# Counter_Display_v2_OLD.net
KiCad netlist of a schematic drawn in Altium Designer
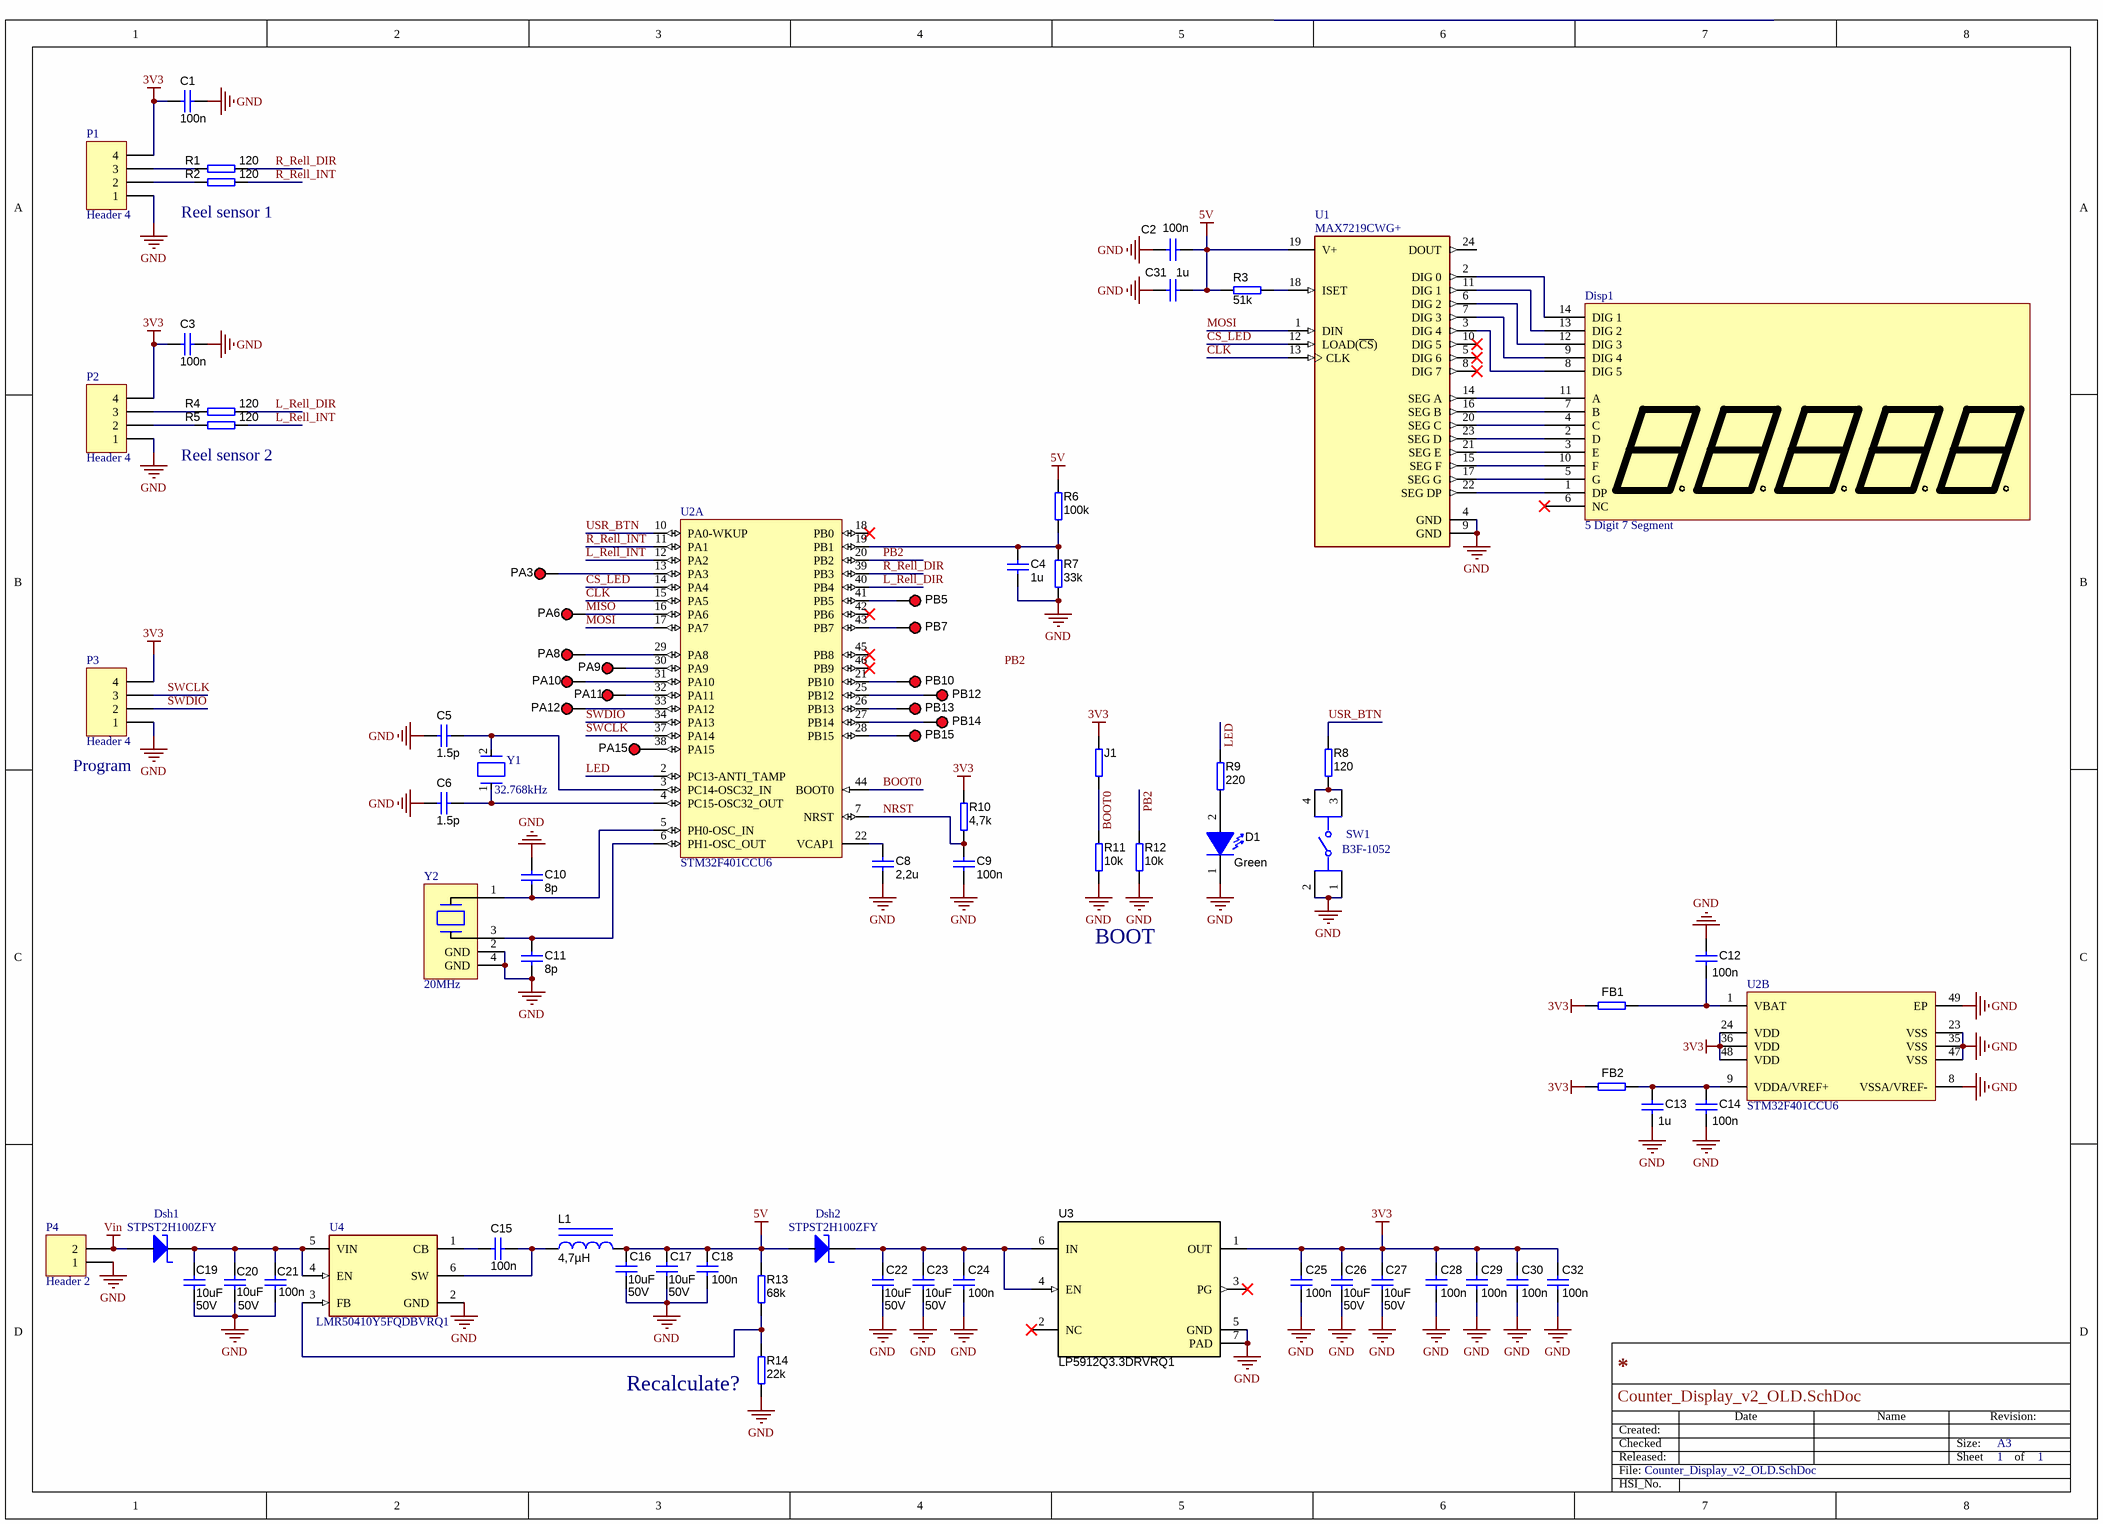
[diagram p0: Counter_Display_v2_OLD.SchDoc]

(export (version "E")
  (design (tool "Eeschema 10.0.6"))
  (components
    (comp (ref "C1")
      (value "100n")
      (footprint "0805_HV")
      (description "CAP, CERM, +/- 10%, X7S,  0805")
      (libsource (lib "Const_Cur_Source") (part "C0805"))
    )
    (comp (ref "C2")
      (value "100n")
      (footprint "0805_HV")
      (description "CAP, CERM, +/- 10%, X7S,  0805")
      (libsource (lib "Const_Cur_Source") (part "C0805"))
    )
    (comp (ref "C3")
      (value "100n")
      (footprint "0805_HV")
      (description "CAP, CERM, +/- 10%, X7S,  0805")
      (libsource (lib "Const_Cur_Source") (part "C0805"))
    )
    (comp (ref "C4")
      (value "1u")
      (footprint "0805_HV")
      (description "CAP, CERM, +/- 10%, X7S,  0805")
      (libsource (lib "Const_Cur_Source") (part "C0805"))
    )
    (comp (ref "C5")
      (value "1.5p")
      (footprint "0805_HV")
      (description "CAP, CERM, +/- 10%, X7S,  0805")
      (libsource (lib "Const_Cur_Source") (part "C0805"))
    )
    (comp (ref "C6")
      (value "1.5p")
      (footprint "0805_HV")
      (description "CAP, CERM, +/- 10%, X7S,  0805")
      (libsource (lib "Const_Cur_Source") (part "C0805"))
    )
    (comp (ref "C8")
      (value "2,2u")
      (footprint "0805_HV")
      (description "CAP, CERM, +/- 10%, X7S,  0805")
      (libsource (lib "Const_Cur_Source") (part "C0805"))
    )
    (comp (ref "C9")
      (value "100n")
      (footprint "0805_HV")
      (description "CAP, CERM, +/- 10%, X7S,  0805")
      (libsource (lib "Const_Cur_Source") (part "C0805"))
    )
    (comp (ref "C10")
      (value "8p")
      (footprint "0805_HV")
      (description "CAP, CERM, +/- 10%, X7S,  0805")
      (libsource (lib "Const_Cur_Source") (part "C0805"))
    )
    (comp (ref "C11")
      (value "8p")
      (footprint "0805_HV")
      (description "CAP, CERM, +/- 10%, X7S,  0805")
      (libsource (lib "Const_Cur_Source") (part "C0805"))
    )
    (comp (ref "C12")
      (value "100n")
      (footprint "0805_HV")
      (description "CAP, CERM, +/- 10%, X7S,  0805")
      (libsource (lib "Const_Cur_Source") (part "C0805"))
    )
    (comp (ref "C13")
      (value "1u")
      (footprint "0805_HV")
      (description "CAP, CERM, +/- 10%, X7S,  0805")
      (libsource (lib "Const_Cur_Source") (part "C0805"))
    )
    (comp (ref "C14")
      (value "100n")
      (footprint "0805_HV")
      (description "CAP, CERM, +/- 10%, X7S,  0805")
      (libsource (lib "Const_Cur_Source") (part "C0805"))
    )
    (comp (ref "C15")
      (value "100n")
      (footprint "0805_HV")
      (description "CAP, CERM, +/- 10%, X7S,  0805")
      (libsource (lib "Const_Cur_Source") (part "C0805"))
    )
    (comp (ref "C16")
      (value "10uF")
      (footprint "1206_180")
      (description "CAP, CERM, NP0, 1206")
      (fields (field (name "VALUE1") "50V"))
      (libsource (lib "Const_Cur_Source") (part "C1206"))
    )
    (comp (ref "C17")
      (value "10uF")
      (footprint "1206_180")
      (description "CAP, CERM, NP0, 1206")
      (fields (field (name "VALUE1") "50V"))
      (libsource (lib "Const_Cur_Source") (part "C1206"))
    )
    (comp (ref "C18")
      (value "100n")
      (footprint "0805_HV")
      (description "CAP, CERM, +/- 10%, X7S,  0805")
      (libsource (lib "Const_Cur_Source") (part "C0805"))
    )
    (comp (ref "C19")
      (value "10uF")
      (footprint "1206_180")
      (description "CAP, CERM, NP0, 1206")
      (fields (field (name "VALUE1") "50V"))
      (libsource (lib "Const_Cur_Source") (part "C1206"))
    )
    (comp (ref "C20")
      (value "10uF")
      (footprint "1206_180")
      (description "CAP, CERM, NP0, 1206")
      (fields (field (name "VALUE1") "50V"))
      (libsource (lib "Const_Cur_Source") (part "C1206"))
    )
    (comp (ref "C21")
      (value "100n")
      (footprint "0805_HV")
      (description "CAP, CERM, +/- 10%, X7S,  0805")
      (libsource (lib "Const_Cur_Source") (part "C0805"))
    )
    (comp (ref "C22")
      (value "10uF")
      (footprint "1206_180")
      (description "CAP, CERM, NP0, 1206")
      (fields (field (name "VALUE1") "50V"))
      (libsource (lib "Const_Cur_Source") (part "C1206"))
    )
    (comp (ref "C23")
      (value "10uF")
      (footprint "1206_180")
      (description "CAP, CERM, NP0, 1206")
      (fields (field (name "VALUE1") "50V"))
      (libsource (lib "Const_Cur_Source") (part "C1206"))
    )
    (comp (ref "C24")
      (value "100n")
      (footprint "0805_HV")
      (description "CAP, CERM, +/- 10%, X7S,  0805")
      (libsource (lib "Const_Cur_Source") (part "C0805"))
    )
    (comp (ref "C25")
      (value "100n")
      (footprint "0805_HV")
      (description "CAP, CERM, +/- 10%, X7S,  0805")
      (libsource (lib "Const_Cur_Source") (part "C0805"))
    )
    (comp (ref "C26")
      (value "10uF")
      (footprint "1206_180")
      (description "CAP, CERM, NP0, 1206")
      (fields (field (name "VALUE1") "50V"))
      (libsource (lib "Const_Cur_Source") (part "C1206"))
    )
    (comp (ref "C27")
      (value "10uF")
      (footprint "1206_180")
      (description "CAP, CERM, NP0, 1206")
      (fields (field (name "VALUE1") "50V"))
      (libsource (lib "Const_Cur_Source") (part "C1206"))
    )
    (comp (ref "C28")
      (value "100n")
      (footprint "0805_HV")
      (description "CAP, CERM, +/- 10%, X7S,  0805")
      (libsource (lib "Const_Cur_Source") (part "C0805"))
    )
    (comp (ref "C29")
      (value "100n")
      (footprint "0805_HV")
      (description "CAP, CERM, +/- 10%, X7S,  0805")
      (libsource (lib "Const_Cur_Source") (part "C0805"))
    )
    (comp (ref "C30")
      (value "100n")
      (footprint "0805_HV")
      (description "CAP, CERM, +/- 10%, X7S,  0805")
      (libsource (lib "Const_Cur_Source") (part "C0805"))
    )
    (comp (ref "C31")
      (value "1u")
      (footprint "0805_HV")
      (description "CAP, CERM, +/- 10%, X7S,  0805")
      (libsource (lib "Const_Cur_Source") (part "C0805"))
    )
    (comp (ref "C32")
      (value "100n")
      (footprint "0805_HV")
      (description "CAP, CERM, +/- 10%, X7S,  0805")
      (libsource (lib "Const_Cur_Source") (part "C0805"))
    )
    (comp (ref "D1")
      (value "Green")
      (footprint "WL-SMCW_GREEN")
      (description "LED, Green, SMD")
      (fields
        (field (name "MANUFACTURER") "Wurth Elektronik")
        (field (name "PARTNUMBER") "150060GS75000")
        (field (name "PUBLISHER") "Texas Instruments")
      )
      (libsource (lib "DCDC_SCH_Lib") (part "150060GS75000"))
    )
    (comp (ref "Disp1")
      (value "5 Digit 7 Segment")
      (footprint "5 Digit 7 Seg LED")
      (description "0,2\" 7 Segment LED 5 Digit Display")
      (libsource (lib "Const_Cur_Source") (part "5 Digit 7 Segment"))
    )
    (comp (ref "Dsh1")
      (value "STPST2H100ZFY")
      (footprint "ONSC-SOD-123-2-425-04_V")
      (description "Diode Shottky")
      (fields (field (name "Comment") "DIODE_Shottky"))
      (libsource (lib "Const_Cur_Source") (part "DIODE_Shottky"))
    )
    (comp (ref "Dsh2")
      (value "STPST2H100ZFY")
      (footprint "ONSC-SOD-123-2-425-04_V")
      (description "Diode Shottky")
      (fields (field (name "Comment") "DIODE_Shottky"))
      (libsource (lib "Const_Cur_Source") (part "DIODE_Shottky"))
    )
    (comp (ref "FB1")
      (value "~")
      (footprint "0805_HV")
      (description "RES, 1%, 0.1 W, 0805")
      (libsource (lib "Const_Cur_Source") (part "R0805"))
    )
    (comp (ref "FB2")
      (value "~")
      (footprint "0805_HV")
      (description "RES, 1%, 0.1 W, 0805")
      (libsource (lib "Const_Cur_Source") (part "R0805"))
    )
    (comp (ref "J1")
      (value "~")
      (footprint "0805_HV")
      (description "RES, 1%, 0.1 W, 0805")
      (libsource (lib "Const_Cur_Source") (part "R0805"))
    )
    (comp (ref "L1")
      (value "MSS5121-333MLB")
      (footprint "MSS5121")
      (description "Inductor, Shielded Drum Core, Ferrite, 33 µH, 0.67 A, 0.48 ohm, SMD")
      (fields
        (field (name "VALUEDISPLAYED") "4,7µH")
        (field (name "MANUFACTURER") "Coilcraft")
        (field (name "PUBLISHER") "Texas Instruments")
      )
      (libsource (lib "Inductor_Coilcraft") (part "MSS5121-333MLB"))
    )
    (comp (ref "P1")
      (value "Header 4")
      (footprint "4-Pol. Connector")
      (description "Header, 4-Pin")
      (fields (field (name "PUBLISHER") "Altium Limited"))
      (libsource (lib "Miscellaneous Connectors") (part "Header 4"))
    )
    (comp (ref "P2")
      (value "Header 4")
      (footprint "4-Pol. Connector")
      (description "Header, 4-Pin")
      (fields (field (name "PUBLISHER") "Altium Limited"))
      (libsource (lib "Miscellaneous Connectors") (part "Header 4"))
    )
    (comp (ref "P3")
      (value "Header 4")
      (footprint "HDR1X4")
      (description "Header, 4-Pin")
      (fields (field (name "PUBLISHER") "Altium Limited"))
      (libsource (lib "Miscellaneous Connectors") (part "Header 4"))
    )
    (comp (ref "P4")
      (value "Header 2")
      (footprint "HDR1X2")
      (description "Header, 2-Pin")
      (fields (field (name "PUBLISHER") "Altium Limited"))
      (libsource (lib "Miscellaneous Connectors") (part "Header 2"))
    )
    (comp (ref "PA3")
      (value "~")
      (footprint "TP")
      (description "Test Point, Miniature, Red, TH")
      (fields
        (field (name "PARTNUMBER") "5000")
        (field (name "MANUFACTURER") "Keystone")
        (field (name "PUBLISHER") "Texas Instruments")
      )
      (libsource (lib "Const_Cur_Source") (part "TP"))
    )
    (comp (ref "PA6")
      (value "~")
      (footprint "TP")
      (description "Test Point, Miniature, Red, TH")
      (fields
        (field (name "PARTNUMBER") "5000")
        (field (name "MANUFACTURER") "Keystone")
        (field (name "PUBLISHER") "Texas Instruments")
      )
      (libsource (lib "Const_Cur_Source") (part "TP"))
    )
    (comp (ref "PA8")
      (value "~")
      (footprint "TP")
      (description "Test Point, Miniature, Red, TH")
      (fields
        (field (name "PARTNUMBER") "5000")
        (field (name "MANUFACTURER") "Keystone")
        (field (name "PUBLISHER") "Texas Instruments")
      )
      (libsource (lib "Const_Cur_Source") (part "TP"))
    )
    (comp (ref "PA9")
      (value "~")
      (footprint "TP")
      (description "Test Point, Miniature, Red, TH")
      (fields
        (field (name "PARTNUMBER") "5000")
        (field (name "MANUFACTURER") "Keystone")
        (field (name "PUBLISHER") "Texas Instruments")
      )
      (libsource (lib "Const_Cur_Source") (part "TP"))
    )
    (comp (ref "PA10")
      (value "~")
      (footprint "TP")
      (description "Test Point, Miniature, Red, TH")
      (fields
        (field (name "PARTNUMBER") "5000")
        (field (name "MANUFACTURER") "Keystone")
        (field (name "PUBLISHER") "Texas Instruments")
      )
      (libsource (lib "Const_Cur_Source") (part "TP"))
    )
    (comp (ref "PA11")
      (value "~")
      (footprint "TP")
      (description "Test Point, Miniature, Red, TH")
      (fields
        (field (name "PARTNUMBER") "5000")
        (field (name "MANUFACTURER") "Keystone")
        (field (name "PUBLISHER") "Texas Instruments")
      )
      (libsource (lib "Const_Cur_Source") (part "TP"))
    )
    (comp (ref "PA12")
      (value "~")
      (footprint "TP")
      (description "Test Point, Miniature, Red, TH")
      (fields
        (field (name "PARTNUMBER") "5000")
        (field (name "MANUFACTURER") "Keystone")
        (field (name "PUBLISHER") "Texas Instruments")
      )
      (libsource (lib "Const_Cur_Source") (part "TP"))
    )
    (comp (ref "PA15")
      (value "~")
      (footprint "TP")
      (description "Test Point, Miniature, Red, TH")
      (fields
        (field (name "PARTNUMBER") "5000")
        (field (name "MANUFACTURER") "Keystone")
        (field (name "PUBLISHER") "Texas Instruments")
      )
      (libsource (lib "Const_Cur_Source") (part "TP"))
    )
    (comp (ref "PB5")
      (value "~")
      (footprint "TP")
      (description "Test Point, Miniature, Red, TH")
      (fields
        (field (name "PARTNUMBER") "5000")
        (field (name "MANUFACTURER") "Keystone")
        (field (name "PUBLISHER") "Texas Instruments")
      )
      (libsource (lib "Const_Cur_Source") (part "TP"))
    )
    (comp (ref "PB7")
      (value "~")
      (footprint "TP")
      (description "Test Point, Miniature, Red, TH")
      (fields
        (field (name "PARTNUMBER") "5000")
        (field (name "MANUFACTURER") "Keystone")
        (field (name "PUBLISHER") "Texas Instruments")
      )
      (libsource (lib "Const_Cur_Source") (part "TP"))
    )
    (comp (ref "PB10")
      (value "~")
      (footprint "TP")
      (description "Test Point, Miniature, Red, TH")
      (fields
        (field (name "PARTNUMBER") "5000")
        (field (name "MANUFACTURER") "Keystone")
        (field (name "PUBLISHER") "Texas Instruments")
      )
      (libsource (lib "Const_Cur_Source") (part "TP"))
    )
    (comp (ref "PB12")
      (value "~")
      (footprint "TP")
      (description "Test Point, Miniature, Red, TH")
      (fields
        (field (name "PARTNUMBER") "5000")
        (field (name "MANUFACTURER") "Keystone")
        (field (name "PUBLISHER") "Texas Instruments")
      )
      (libsource (lib "Const_Cur_Source") (part "TP"))
    )
    (comp (ref "PB13")
      (value "~")
      (footprint "TP")
      (description "Test Point, Miniature, Red, TH")
      (fields
        (field (name "PARTNUMBER") "5000")
        (field (name "MANUFACTURER") "Keystone")
        (field (name "PUBLISHER") "Texas Instruments")
      )
      (libsource (lib "Const_Cur_Source") (part "TP"))
    )
    (comp (ref "PB14")
      (value "~")
      (footprint "TP")
      (description "Test Point, Miniature, Red, TH")
      (fields
        (field (name "PARTNUMBER") "5000")
        (field (name "MANUFACTURER") "Keystone")
        (field (name "PUBLISHER") "Texas Instruments")
      )
      (libsource (lib "Const_Cur_Source") (part "TP"))
    )
    (comp (ref "PB15")
      (value "~")
      (footprint "TP")
      (description "Test Point, Miniature, Red, TH")
      (fields
        (field (name "PARTNUMBER") "5000")
        (field (name "MANUFACTURER") "Keystone")
        (field (name "PUBLISHER") "Texas Instruments")
      )
      (libsource (lib "Const_Cur_Source") (part "TP"))
    )
    (comp (ref "R1")
      (value "120")
      (footprint "0805_HV")
      (description "RES, 1%, 0.1 W, 0805")
      (libsource (lib "Const_Cur_Source") (part "R0805"))
    )
    (comp (ref "R2")
      (value "120")
      (footprint "0805_HV")
      (description "RES, 1%, 0.1 W, 0805")
      (libsource (lib "Const_Cur_Source") (part "R0805"))
    )
    (comp (ref "R3")
      (value "51k")
      (footprint "0805_HV")
      (description "RES, 1%, 0.1 W, 0805")
      (libsource (lib "Const_Cur_Source") (part "R0805"))
    )
    (comp (ref "R4")
      (value "120")
      (footprint "0805_HV")
      (description "RES, 1%, 0.1 W, 0805")
      (libsource (lib "Const_Cur_Source") (part "R0805"))
    )
    (comp (ref "R5")
      (value "120")
      (footprint "0805_HV")
      (description "RES, 1%, 0.1 W, 0805")
      (libsource (lib "Const_Cur_Source") (part "R0805"))
    )
    (comp (ref "R6")
      (value "100k")
      (footprint "0805_HV")
      (description "RES, 1%, 0.1 W, 0805")
      (libsource (lib "Const_Cur_Source") (part "R0805"))
    )
    (comp (ref "R7")
      (value "33k")
      (footprint "0805_HV")
      (description "RES, 1%, 0.1 W, 0805")
      (libsource (lib "Const_Cur_Source") (part "R0805"))
    )
    (comp (ref "R8")
      (value "120")
      (footprint "0805_HV")
      (description "RES, 1%, 0.1 W, 0805")
      (libsource (lib "Const_Cur_Source") (part "R0805"))
    )
    (comp (ref "R9")
      (value "220")
      (footprint "0805_HV")
      (description "RES, 1%, 0.1 W, 0805")
      (libsource (lib "Const_Cur_Source") (part "R0805"))
    )
    (comp (ref "R10")
      (value "4,7k")
      (footprint "0805_HV")
      (description "RES, 1%, 0.1 W, 0805")
      (libsource (lib "Const_Cur_Source") (part "R0805"))
    )
    (comp (ref "R11")
      (value "10k")
      (footprint "0805_HV")
      (description "RES, 1%, 0.1 W, 0805")
      (libsource (lib "Const_Cur_Source") (part "R0805"))
    )
    (comp (ref "R12")
      (value "10k")
      (footprint "0805_HV")
      (description "RES, 1%, 0.1 W, 0805")
      (libsource (lib "Const_Cur_Source") (part "R0805"))
    )
    (comp (ref "R13")
      (value "68k")
      (footprint "0805_HV")
      (description "RES, 1%, 0.1 W, 0805")
      (libsource (lib "Const_Cur_Source") (part "R0805"))
    )
    (comp (ref "R14")
      (value "22k")
      (footprint "0805_HV")
      (description "RES, 1%, 0.1 W, 0805")
      (libsource (lib "Const_Cur_Source") (part "R0805"))
    )
    (comp (ref "SW1")
      (value "B3F-1052")
      (footprint "Omron_B3F-1052_0")
      (libsource (lib "Const_Cur_Source") (part "B3F-1052"))
    )
    (comp (ref "U1")
      (value "MAX7219CWG+")
      (footprint "Maxim_Integrated_W24-1_IPC_A")
      (libsource (lib "Const_Cur_Source") (part "MAX7219CWG+"))
    )
    (comp (ref "U2")
      (value "STM32F401CCU6")
      (footprint "STM-UFQFPN48_M")
      (fields (field (name "MANUFACTURER") "STMicroelectronics"))
      (libsource (lib "Const_Cur_Source") (part "STM32F401CCU6"))
    )
    (comp (ref "U3")
      (value "LP5912Q3.3DRVRQ1")
      (footprint "DRV0006A")
      (fields
        (field (name "ALTERNATE PARTNUMBER") "LP5912Q3.3DRVTQ1")
        (field (name "MANUFACTURER") "Texas Instruments")
        (field (name "SYMBOLCREATOR") "a0411947")
        (field (name "PUBLISHER") "Texas Instruments")
      )
      (libsource (lib "TI_Pre_Release1") (part "LP5912Q3.3DRVRQ1"))
    )
    (comp (ref "U4")
      (value "LMR50410Y5FQDBVRQ1")
      (footprint "Texas_Instruments_DBV0006A_IPC_A")
      (libsource (lib "Const_Cur_Source") (part "LMR50410Y5FQDBVRQ1"))
    )
    (comp (ref "Y1")
      (value "Qartz_32,768kHz")
      (footprint "Quartz_32.768kHz")
      (description "CRYS")
      (fields
        (field (name "MANUFACTURER") "Euroquartz")
        (field (name "OCTOPART PART NUMBER") "45978c55d5b29a50")
        (field (name "PART NUMBER") "32.768kHz")
      )
      (libsource (lib "Const_Cur_Source") (part "Qartz_32,768kHz"))
    )
    (comp (ref "Y2")
      (value "Qartz_20MHz")
      (footprint "Crystal Oscilator 25MHz")
      (description "CRYS")
      (fields
        (field (name "MANUFACTURER") "Euroquartz")
        (field (name "OCTOPART PART NUMBER") "45978c55d5b29a50")
        (field (name "PART NUMBER") "20MHz")
      )
      (libsource (lib "Const_Cur_Source") (part "Qartz_20MHz"))
    )
  )
  (nets
    (net (code "1") (name "/BOOT0") (class "Default")
      (node (ref "J1") (pin "1") (pinfunction "1_1") (pintype "passive"))
      (node (ref "R11") (pin "2") (pinfunction "2_2") (pintype "passive"))
      (node (ref "U2") (pin "44") (pinfunction "BOOT0_44") (pintype "input"))
    )
    (net (code "2") (name "/CLK") (class "Default")
      (node (ref "U1") (pin "13") (pinfunction "CLK_13") (pintype "input"))
      (node (ref "U2") (pin "15") (pinfunction "PA5_15") (pintype "bidirectional"))
    )
    (net (code "3") (name "/CS_LED") (class "Default")
      (node (ref "U1") (pin "12") (pinfunction "LOAD(~{CS})_12") (pintype "input"))
      (node (ref "U2") (pin "14") (pinfunction "PA4_14") (pintype "bidirectional"))
    )
    (net (code "4") (name "/LED") (class "Default")
      (node (ref "R9") (pin "2") (pinfunction "2_2") (pintype "passive"))
      (node (ref "U2") (pin "2") (pinfunction "PC13-ANTI_TAMP_2") (pintype "bidirectional"))
    )
    (net (code "5") (name "/L_Rell_DIR") (class "Default")
      (node (ref "R4") (pin "2") (pinfunction "2_2") (pintype "passive"))
      (node (ref "U2") (pin "40") (pinfunction "PB4_40") (pintype "bidirectional"))
    )
    (net (code "6") (name "/L_Rell_INT") (class "Default")
      (node (ref "R5") (pin "2") (pinfunction "2_2") (pintype "passive"))
      (node (ref "U2") (pin "12") (pinfunction "PA2_12") (pintype "bidirectional"))
    )
    (net (code "7") (name "/MISO") (class "Default")
      (node (ref "PA6") (pin "1") (pintype "passive"))
      (node (ref "U2") (pin "16") (pinfunction "PA6_16") (pintype "bidirectional"))
    )
    (net (code "8") (name "/MOSI") (class "Default")
      (node (ref "U1") (pin "1") (pinfunction "DIN_1") (pintype "input"))
      (node (ref "U2") (pin "17") (pinfunction "PA7_17") (pintype "bidirectional"))
    )
    (net (code "9") (name "/NRST") (class "Default")
      (node (ref "C9") (pin "2") (pinfunction "2_2") (pintype "passive"))
      (node (ref "R10") (pin "1") (pinfunction "1_1") (pintype "passive"))
      (node (ref "U2") (pin "7") (pinfunction "NRST_7") (pintype "bidirectional"))
    )
    (net (code "10") (name "/PB2") (class "Default")
      (node (ref "R12") (pin "2") (pinfunction "2_2") (pintype "passive"))
      (node (ref "U2") (pin "20") (pinfunction "PB2_20") (pintype "bidirectional"))
    )
    (net (code "11") (name "/R_Rell_DIR") (class "Default")
      (node (ref "R1") (pin "2") (pinfunction "2_2") (pintype "passive"))
      (node (ref "U2") (pin "39") (pinfunction "PB3_39") (pintype "bidirectional"))
    )
    (net (code "12") (name "/R_Rell_INT") (class "Default")
      (node (ref "R2") (pin "2") (pinfunction "2_2") (pintype "passive"))
      (node (ref "U2") (pin "11") (pinfunction "PA1_11") (pintype "bidirectional"))
    )
    (net (code "13") (name "/SWCLK") (class "Default")
      (node (ref "P3") (pin "3") (pinfunction "3_3") (pintype "passive"))
      (node (ref "U2") (pin "37") (pinfunction "PA14_37") (pintype "bidirectional"))
    )
    (net (code "14") (name "/SWDIO") (class "Default")
      (node (ref "P3") (pin "2") (pinfunction "2_2") (pintype "passive"))
      (node (ref "U2") (pin "34") (pinfunction "PA13_34") (pintype "bidirectional"))
    )
    (net (code "15") (name "/USR_BTN") (class "Default")
      (node (ref "R8") (pin "2") (pinfunction "2_2") (pintype "passive"))
      (node (ref "U2") (pin "10") (pinfunction "PA0-WKUP_10") (pintype "bidirectional"))
    )
    (net (code "16") (name "3V3") (class "Default")
      (node (ref "C1") (pin "1") (pinfunction "1_1") (pintype "passive"))
      (node (ref "C25") (pin "1") (pinfunction "1_1") (pintype "passive"))
      (node (ref "C26") (pin "1") (pinfunction "1_1") (pintype "passive"))
      (node (ref "C27") (pin "1") (pinfunction "1_1") (pintype "passive"))
      (node (ref "C28") (pin "1") (pinfunction "1_1") (pintype "passive"))
      (node (ref "C29") (pin "1") (pinfunction "1_1") (pintype "passive"))
      (node (ref "C3") (pin "1") (pinfunction "1_1") (pintype "passive"))
      (node (ref "C30") (pin "1") (pinfunction "1_1") (pintype "passive"))
      (node (ref "C32") (pin "1") (pinfunction "1_1") (pintype "passive"))
      (node (ref "FB1") (pin "2") (pinfunction "2_2") (pintype "passive"))
      (node (ref "FB2") (pin "2") (pinfunction "2_2") (pintype "passive"))
      (node (ref "J1") (pin "2") (pinfunction "2_2") (pintype "passive"))
      (node (ref "P1") (pin "4") (pinfunction "4_4") (pintype "passive"))
      (node (ref "P2") (pin "4") (pinfunction "4_4") (pintype "passive"))
      (node (ref "P3") (pin "4") (pinfunction "4_4") (pintype "passive"))
      (node (ref "R10") (pin "2") (pinfunction "2_2") (pintype "passive"))
      (node (ref "U2") (pin "24") (pinfunction "VDD_24") (pintype "power_in"))
      (node (ref "U2") (pin "36") (pinfunction "VDD_36") (pintype "power_in"))
      (node (ref "U2") (pin "48") (pinfunction "VDD_48") (pintype "power_in"))
      (node (ref "U3") (pin "1") (pinfunction "OUT_1") (pintype "power_in"))
    )
    (net (code "17") (name "5V") (class "Default")
      (node (ref "C16") (pin "1") (pinfunction "1_1") (pintype "passive"))
      (node (ref "C17") (pin "1") (pinfunction "1_1") (pintype "passive"))
      (node (ref "C18") (pin "1") (pinfunction "1_1") (pintype "passive"))
      (node (ref "C2") (pin "2") (pinfunction "2_2") (pintype "passive"))
      (node (ref "C31") (pin "2") (pinfunction "2_2") (pintype "passive"))
      (node (ref "Dsh2") (pin "A") (pinfunction "A_A") (pintype "passive"))
      (node (ref "L1") (pin "2") (pinfunction "2_2") (pintype "passive"))
      (node (ref "R13") (pin "1") (pinfunction "1_1") (pintype "passive"))
      (node (ref "R3") (pin "1") (pinfunction "1_1") (pintype "passive"))
      (node (ref "R6") (pin "1") (pinfunction "1_1") (pintype "passive"))
      (node (ref "U1") (pin "19") (pinfunction "V+_19") (pintype "power_in"))
    )
    (net (code "18") (name "GND") (class "Default")
      (node (ref "C1") (pin "2") (pinfunction "2_2") (pintype "passive"))
      (node (ref "C10") (pin "1") (pinfunction "1_1") (pintype "passive"))
      (node (ref "C11") (pin "2") (pinfunction "2_2") (pintype "passive"))
      (node (ref "C12") (pin "1") (pinfunction "1_1") (pintype "passive"))
      (node (ref "C13") (pin "2") (pinfunction "2_2") (pintype "passive"))
      (node (ref "C14") (pin "2") (pinfunction "2_2") (pintype "passive"))
      (node (ref "C16") (pin "2") (pinfunction "2_2") (pintype "passive"))
      (node (ref "C17") (pin "2") (pinfunction "2_2") (pintype "passive"))
      (node (ref "C18") (pin "2") (pinfunction "2_2") (pintype "passive"))
      (node (ref "C19") (pin "2") (pinfunction "2_2") (pintype "passive"))
      (node (ref "C2") (pin "1") (pinfunction "1_1") (pintype "passive"))
      (node (ref "C20") (pin "2") (pinfunction "2_2") (pintype "passive"))
      (node (ref "C21") (pin "2") (pinfunction "2_2") (pintype "passive"))
      (node (ref "C22") (pin "2") (pinfunction "2_2") (pintype "passive"))
      (node (ref "C23") (pin "2") (pinfunction "2_2") (pintype "passive"))
      (node (ref "C24") (pin "2") (pinfunction "2_2") (pintype "passive"))
      (node (ref "C25") (pin "2") (pinfunction "2_2") (pintype "passive"))
      (node (ref "C26") (pin "2") (pinfunction "2_2") (pintype "passive"))
      (node (ref "C27") (pin "2") (pinfunction "2_2") (pintype "passive"))
      (node (ref "C28") (pin "2") (pinfunction "2_2") (pintype "passive"))
      (node (ref "C29") (pin "2") (pinfunction "2_2") (pintype "passive"))
      (node (ref "C3") (pin "2") (pinfunction "2_2") (pintype "passive"))
      (node (ref "C30") (pin "2") (pinfunction "2_2") (pintype "passive"))
      (node (ref "C31") (pin "1") (pinfunction "1_1") (pintype "passive"))
      (node (ref "C32") (pin "2") (pinfunction "2_2") (pintype "passive"))
      (node (ref "C4") (pin "2") (pinfunction "2_2") (pintype "passive"))
      (node (ref "C5") (pin "1") (pinfunction "1_1") (pintype "passive"))
      (node (ref "C6") (pin "1") (pinfunction "1_1") (pintype "passive"))
      (node (ref "C8") (pin "2") (pinfunction "2_2") (pintype "passive"))
      (node (ref "C9") (pin "1") (pinfunction "1_1") (pintype "passive"))
      (node (ref "D1") (pin "1") (pinfunction "K_1") (pintype "passive"))
      (node (ref "P1") (pin "1") (pinfunction "1_1") (pintype "passive"))
      (node (ref "P2") (pin "1") (pinfunction "1_1") (pintype "passive"))
      (node (ref "P3") (pin "1") (pinfunction "1_1") (pintype "passive"))
      (node (ref "P4") (pin "1") (pinfunction "1_1") (pintype "passive"))
      (node (ref "R11") (pin "1") (pinfunction "1_1") (pintype "passive"))
      (node (ref "R12") (pin "1") (pinfunction "1_1") (pintype "passive"))
      (node (ref "R14") (pin "2") (pinfunction "2_2") (pintype "passive"))
      (node (ref "R7") (pin "2") (pinfunction "2_2") (pintype "passive"))
      (node (ref "SW1") (pin "1") (pinfunction "1_1") (pintype "passive"))
      (node (ref "SW1") (pin "2") (pinfunction "2_2") (pintype "passive"))
      (node (ref "U1") (pin "4") (pinfunction "GND_4") (pintype "power_in"))
      (node (ref "U1") (pin "9") (pinfunction "GND_9") (pintype "power_in"))
      (node (ref "U2") (pin "23") (pinfunction "VSS_23") (pintype "power_in"))
      (node (ref "U2") (pin "35") (pinfunction "VSS_35") (pintype "power_in"))
      (node (ref "U2") (pin "47") (pinfunction "VSS_47") (pintype "power_in"))
      (node (ref "U2") (pin "49") (pinfunction "EP_49") (pintype "power_in"))
      (node (ref "U2") (pin "8") (pinfunction "VSSA/VREF-_8") (pintype "power_in"))
      (node (ref "U3") (pin "5") (pinfunction "GND_5") (pintype "power_in"))
      (node (ref "U3") (pin "7") (pinfunction "PAD_7") (pintype "power_in"))
      (node (ref "U4") (pin "2") (pinfunction "GND_2") (pintype "power_in"))
      (node (ref "Y2") (pin "2") (pinfunction "GND_2") (pintype "passive"))
      (node (ref "Y2") (pin "4") (pinfunction "GND_4") (pintype "passive"))
    )
    (net (code "19") (name "Net-(D1-A)") (class "Default")
      (node (ref "D1") (pin "2") (pinfunction "A_2") (pintype "passive"))
      (node (ref "R9") (pin "1") (pinfunction "1_1") (pintype "passive"))
    )
    (net (code "20") (name "Net-(Disp1-A)") (class "Default")
      (node (ref "Disp1") (pin "11") (pinfunction "A_11") (pintype "passive"))
      (node (ref "U1") (pin "14") (pinfunction "SEG_A_14") (pintype "output"))
    )
    (net (code "21") (name "Net-(Disp1-B)") (class "Default")
      (node (ref "Disp1") (pin "7") (pinfunction "B_7") (pintype "passive"))
      (node (ref "U1") (pin "16") (pinfunction "SEG_B_16") (pintype "output"))
    )
    (net (code "22") (name "Net-(Disp1-C)") (class "Default")
      (node (ref "Disp1") (pin "4") (pinfunction "C_4") (pintype "passive"))
      (node (ref "U1") (pin "20") (pinfunction "SEG_C_20") (pintype "output"))
    )
    (net (code "23") (name "Net-(Disp1-D)") (class "Default")
      (node (ref "Disp1") (pin "2") (pinfunction "D_2") (pintype "passive"))
      (node (ref "U1") (pin "23") (pinfunction "SEG_D_23") (pintype "output"))
    )
    (net (code "24") (name "Net-(Disp1-DIG_1)") (class "Default")
      (node (ref "Disp1") (pin "14") (pinfunction "DIG_1_14") (pintype "passive"))
      (node (ref "U1") (pin "2") (pinfunction "DIG_0_2") (pintype "output"))
    )
    (net (code "25") (name "Net-(Disp1-DIG_2)") (class "Default")
      (node (ref "Disp1") (pin "13") (pinfunction "DIG_2_13") (pintype "passive"))
      (node (ref "U1") (pin "11") (pinfunction "DIG_1_11") (pintype "output"))
    )
    (net (code "26") (name "Net-(Disp1-DIG_3)") (class "Default")
      (node (ref "Disp1") (pin "12") (pinfunction "DIG_3_12") (pintype "passive"))
      (node (ref "U1") (pin "6") (pinfunction "DIG_2_6") (pintype "output"))
    )
    (net (code "27") (name "Net-(Disp1-DIG_4)") (class "Default")
      (node (ref "Disp1") (pin "9") (pinfunction "DIG_4_9") (pintype "passive"))
      (node (ref "U1") (pin "7") (pinfunction "DIG_3_7") (pintype "output"))
    )
    (net (code "28") (name "Net-(Disp1-DIG_5)") (class "Default")
      (node (ref "Disp1") (pin "8") (pinfunction "DIG_5_8") (pintype "passive"))
      (node (ref "U1") (pin "3") (pinfunction "DIG_4_3") (pintype "output"))
    )
    (net (code "29") (name "Net-(Disp1-DP)") (class "Default")
      (node (ref "Disp1") (pin "1") (pinfunction "DP_1") (pintype "passive"))
      (node (ref "U1") (pin "22") (pinfunction "SEG_DP_22") (pintype "output"))
    )
    (net (code "30") (name "Net-(Disp1-E)") (class "Default")
      (node (ref "Disp1") (pin "3") (pinfunction "E_3") (pintype "passive"))
      (node (ref "U1") (pin "21") (pinfunction "SEG_E_21") (pintype "output"))
    )
    (net (code "31") (name "Net-(Disp1-F)") (class "Default")
      (node (ref "Disp1") (pin "10") (pinfunction "F_10") (pintype "passive"))
      (node (ref "U1") (pin "15") (pinfunction "SEG_F_15") (pintype "output"))
    )
    (net (code "32") (name "Net-(Disp1-G)") (class "Default")
      (node (ref "Disp1") (pin "5") (pinfunction "G_5") (pintype "passive"))
      (node (ref "U1") (pin "17") (pinfunction "SEG_G_17") (pintype "output"))
    )
    (net (code "33") (name "Net-(P1-Pad2)") (class "Default")
      (node (ref "P1") (pin "2") (pinfunction "2_2") (pintype "passive"))
      (node (ref "R2") (pin "1") (pinfunction "1_1") (pintype "passive"))
    )
    (net (code "34") (name "Net-(P1-Pad3)") (class "Default")
      (node (ref "P1") (pin "3") (pinfunction "3_3") (pintype "passive"))
      (node (ref "R1") (pin "1") (pinfunction "1_1") (pintype "passive"))
    )
    (net (code "35") (name "Net-(P2-Pad2)") (class "Default")
      (node (ref "P2") (pin "2") (pinfunction "2_2") (pintype "passive"))
      (node (ref "R5") (pin "1") (pinfunction "1_1") (pintype "passive"))
    )
    (net (code "36") (name "Net-(P2-Pad3)") (class "Default")
      (node (ref "P2") (pin "3") (pinfunction "3_3") (pintype "passive"))
      (node (ref "R4") (pin "1") (pinfunction "1_1") (pintype "passive"))
    )
    (net (code "37") (name "Net-(R8-Pad1)") (class "Default")
      (node (ref "R8") (pin "1") (pinfunction "1_1") (pintype "passive"))
      (node (ref "SW1") (pin "3") (pinfunction "3_3") (pintype "passive"))
      (node (ref "SW1") (pin "4") (pinfunction "4_4") (pintype "passive"))
    )
    (net (code "38") (name "Net-(U1-ISET)") (class "Default")
      (node (ref "R3") (pin "2") (pinfunction "2_2") (pintype "passive"))
      (node (ref "U1") (pin "18") (pinfunction "ISET_18") (pintype "input"))
    )
    (net (code "39") (name "Net-(U2A-PA3)") (class "Default")
      (node (ref "PA3") (pin "1") (pintype "passive"))
      (node (ref "U2") (pin "13") (pinfunction "PA3_13") (pintype "bidirectional"))
    )
    (net (code "40") (name "Net-(U2A-PA8)") (class "Default")
      (node (ref "PA8") (pin "1") (pintype "passive"))
      (node (ref "U2") (pin "29") (pinfunction "PA8_29") (pintype "bidirectional"))
    )
    (net (code "41") (name "Net-(U2A-PA9)") (class "Default")
      (node (ref "PA9") (pin "1") (pintype "passive"))
      (node (ref "U2") (pin "30") (pinfunction "PA9_30") (pintype "bidirectional"))
    )
    (net (code "42") (name "Net-(U2A-PA10)") (class "Default")
      (node (ref "PA10") (pin "1") (pintype "passive"))
      (node (ref "U2") (pin "31") (pinfunction "PA10_31") (pintype "bidirectional"))
    )
    (net (code "43") (name "Net-(U2A-PA11)") (class "Default")
      (node (ref "PA11") (pin "1") (pintype "passive"))
      (node (ref "U2") (pin "32") (pinfunction "PA11_32") (pintype "bidirectional"))
    )
    (net (code "44") (name "Net-(U2A-PA12)") (class "Default")
      (node (ref "PA12") (pin "1") (pintype "passive"))
      (node (ref "U2") (pin "33") (pinfunction "PA12_33") (pintype "bidirectional"))
    )
    (net (code "45") (name "Net-(U2A-PA15)") (class "Default")
      (node (ref "PA15") (pin "1") (pintype "passive"))
      (node (ref "U2") (pin "38") (pinfunction "PA15_38") (pintype "bidirectional"))
    )
    (net (code "46") (name "Net-(U2A-PB1)") (class "Default")
      (node (ref "C4") (pin "1") (pinfunction "1_1") (pintype "passive"))
      (node (ref "R6") (pin "2") (pinfunction "2_2") (pintype "passive"))
      (node (ref "R7") (pin "1") (pinfunction "1_1") (pintype "passive"))
      (node (ref "U2") (pin "19") (pinfunction "PB1_19") (pintype "bidirectional"))
    )
    (net (code "47") (name "Net-(U2A-PB5)") (class "Default")
      (node (ref "PB5") (pin "1") (pintype "passive"))
      (node (ref "U2") (pin "41") (pinfunction "PB5_41") (pintype "bidirectional"))
    )
    (net (code "48") (name "Net-(U2A-PB7)") (class "Default")
      (node (ref "PB7") (pin "1") (pintype "passive"))
      (node (ref "U2") (pin "43") (pinfunction "PB7_43") (pintype "bidirectional"))
    )
    (net (code "49") (name "Net-(U2A-PB10)") (class "Default")
      (node (ref "PB10") (pin "1") (pintype "passive"))
      (node (ref "U2") (pin "21") (pinfunction "PB10_21") (pintype "bidirectional"))
    )
    (net (code "50") (name "Net-(U2A-PB12)") (class "Default")
      (node (ref "PB12") (pin "1") (pintype "passive"))
      (node (ref "U2") (pin "25") (pinfunction "PB12_25") (pintype "bidirectional"))
    )
    (net (code "51") (name "Net-(U2A-PB13)") (class "Default")
      (node (ref "PB13") (pin "1") (pintype "passive"))
      (node (ref "U2") (pin "26") (pinfunction "PB13_26") (pintype "bidirectional"))
    )
    (net (code "52") (name "Net-(U2A-PB14)") (class "Default")
      (node (ref "PB14") (pin "1") (pintype "passive"))
      (node (ref "U2") (pin "27") (pinfunction "PB14_27") (pintype "bidirectional"))
    )
    (net (code "53") (name "Net-(U2A-PB15)") (class "Default")
      (node (ref "PB15") (pin "1") (pintype "passive"))
      (node (ref "U2") (pin "28") (pinfunction "PB15_28") (pintype "bidirectional"))
    )
    (net (code "54") (name "Net-(U2A-PC14-OSC32_IN)") (class "Default")
      (node (ref "C5") (pin "2") (pinfunction "2_2") (pintype "passive"))
      (node (ref "U2") (pin "3") (pinfunction "PC14-OSC32_IN_3") (pintype "bidirectional"))
      (node (ref "Y1") (pin "2") (pinfunction "2_2") (pintype "passive"))
    )
    (net (code "55") (name "Net-(U2A-PC15-OSC32_OUT)") (class "Default")
      (node (ref "C6") (pin "2") (pinfunction "2_2") (pintype "passive"))
      (node (ref "U2") (pin "4") (pinfunction "PC15-OSC32_OUT_4") (pintype "bidirectional"))
      (node (ref "Y1") (pin "1") (pinfunction "1_1") (pintype "passive"))
    )
    (net (code "56") (name "Net-(U2A-PH0-OSC_IN)") (class "Default")
      (node (ref "C10") (pin "2") (pinfunction "2_2") (pintype "passive"))
      (node (ref "U2") (pin "5") (pinfunction "PH0-OSC_IN_5") (pintype "bidirectional"))
      (node (ref "Y2") (pin "1") (pintype "passive"))
    )
    (net (code "57") (name "Net-(U2A-PH1-OSC_OUT)") (class "Default")
      (node (ref "C11") (pin "1") (pinfunction "1_1") (pintype "passive"))
      (node (ref "U2") (pin "6") (pinfunction "PH1-OSC_OUT_6") (pintype "bidirectional"))
      (node (ref "Y2") (pin "3") (pintype "passive"))
    )
    (net (code "58") (name "Net-(U2A-VCAP1)") (class "Default")
      (node (ref "C8") (pin "1") (pinfunction "1_1") (pintype "passive"))
      (node (ref "U2") (pin "22") (pinfunction "VCAP1_22") (pintype "power_in"))
    )
    (net (code "59") (name "Net-(U2B-VBAT)") (class "Default")
      (node (ref "C12") (pin "2") (pinfunction "2_2") (pintype "passive"))
      (node (ref "FB1") (pin "1") (pinfunction "1_1") (pintype "passive"))
      (node (ref "U2") (pin "1") (pinfunction "VBAT_1") (pintype "power_in"))
    )
    (net (code "60") (name "Net-(U2B-VDDA{slash}VREF+)") (class "Default")
      (node (ref "C13") (pin "1") (pinfunction "1_1") (pintype "passive"))
      (node (ref "C14") (pin "1") (pinfunction "1_1") (pintype "passive"))
      (node (ref "FB2") (pin "1") (pinfunction "1_1") (pintype "passive"))
      (node (ref "U2") (pin "9") (pinfunction "VDDA/VREF+_9") (pintype "power_in"))
    )
    (net (code "61") (name "Net-(U3-EN)") (class "Default")
      (node (ref "C22") (pin "1") (pinfunction "1_1") (pintype "passive"))
      (node (ref "C23") (pin "1") (pinfunction "1_1") (pintype "passive"))
      (node (ref "C24") (pin "1") (pinfunction "1_1") (pintype "passive"))
      (node (ref "Dsh2") (pin "K") (pinfunction "K_K") (pintype "passive"))
      (node (ref "U3") (pin "4") (pinfunction "EN_4") (pintype "input"))
      (node (ref "U3") (pin "6") (pinfunction "IN_6") (pintype "power_in"))
    )
    (net (code "62") (name "Net-(U4-CB)") (class "Default")
      (node (ref "C15") (pin "1") (pinfunction "1_1") (pintype "passive"))
      (node (ref "U4") (pin "1") (pinfunction "CB_1") (pintype "passive"))
    )
    (net (code "63") (name "Net-(U4-EN)") (class "Default")
      (node (ref "C19") (pin "1") (pinfunction "1_1") (pintype "passive"))
      (node (ref "C20") (pin "1") (pinfunction "1_1") (pintype "passive"))
      (node (ref "C21") (pin "1") (pinfunction "1_1") (pintype "passive"))
      (node (ref "Dsh1") (pin "K") (pinfunction "K_K") (pintype "passive"))
      (node (ref "U4") (pin "4") (pinfunction "EN_4") (pintype "input"))
      (node (ref "U4") (pin "5") (pinfunction "VIN_5") (pintype "power_in"))
    )
    (net (code "64") (name "Net-(U4-FB)") (class "Default")
      (node (ref "R13") (pin "2") (pinfunction "2_2") (pintype "passive"))
      (node (ref "R14") (pin "1") (pinfunction "1_1") (pintype "passive"))
      (node (ref "U4") (pin "3") (pinfunction "FB_3") (pintype "input"))
    )
    (net (code "65") (name "Net-(U4-SW)") (class "Default")
      (node (ref "C15") (pin "2") (pinfunction "2_2") (pintype "passive"))
      (node (ref "L1") (pin "1") (pinfunction "1_1") (pintype "passive"))
      (node (ref "U4") (pin "6") (pinfunction "SW_6") (pintype "passive"))
    )
    (net (code "66") (name "Vin") (class "Default")
      (node (ref "Dsh1") (pin "A") (pinfunction "A_A") (pintype "passive"))
      (node (ref "P4") (pin "2") (pinfunction "2_2") (pintype "passive"))
    )
    (net (code "67") (name "unconnected-(Disp1-NC-Pad6)") (class "Default")
      (node (ref "Disp1") (pin "6") (pinfunction "NC_6") (pintype "passive+no_connect"))
    )
    (net (code "68") (name "unconnected-(U1-DIG_5-Pad10)") (class "Default")
      (node (ref "U1") (pin "10") (pinfunction "DIG_5_10") (pintype "output+no_connect"))
    )
    (net (code "69") (name "unconnected-(U1-DIG_6-Pad5)") (class "Default")
      (node (ref "U1") (pin "5") (pinfunction "DIG_6_5") (pintype "output+no_connect"))
    )
    (net (code "70") (name "unconnected-(U1-DIG_7-Pad8)") (class "Default")
      (node (ref "U1") (pin "8") (pinfunction "DIG_7_8") (pintype "output+no_connect"))
    )
    (net (code "71") (name "unconnected-(U1-DOUT-Pad24)") (class "Default")
      (node (ref "U1") (pin "24") (pinfunction "DOUT_24") (pintype "output"))
    )
    (net (code "72") (name "unconnected-(U2A-PB0-Pad18)") (class "Default")
      (node (ref "U2") (pin "18") (pinfunction "PB0_18") (pintype "bidirectional+no_connect"))
    )
    (net (code "73") (name "unconnected-(U2A-PB6-Pad42)") (class "Default")
      (node (ref "U2") (pin "42") (pinfunction "PB6_42") (pintype "bidirectional+no_connect"))
    )
    (net (code "74") (name "unconnected-(U2A-PB8-Pad45)") (class "Default")
      (node (ref "U2") (pin "45") (pinfunction "PB8_45") (pintype "bidirectional+no_connect"))
    )
    (net (code "75") (name "unconnected-(U2A-PB9-Pad46)") (class "Default")
      (node (ref "U2") (pin "46") (pinfunction "PB9_46") (pintype "bidirectional+no_connect"))
    )
    (net (code "76") (name "unconnected-(U3-NC-Pad2)") (class "Default")
      (node (ref "U3") (pin "2") (pinfunction "NC_2") (pintype "passive+no_connect"))
    )
    (net (code "77") (name "unconnected-(U3-PG-Pad3)") (class "Default")
      (node (ref "U3") (pin "3") (pinfunction "PG_3") (pintype "output+no_connect"))
    )
  )
)
